# currentDetection.net
KiCad netlist of a schematic drawn in Altium Designer
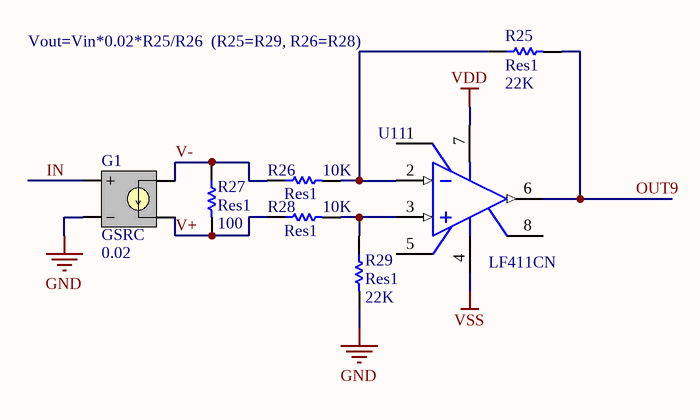
[diagram p0: currentDetection.SchDoc]

(export (version "E")
  (design (tool "Eeschema 10.0.6"))
  (components
    (comp (ref "G1")
      (value "GSRC")
      (description "Voltage Controlled Current Source")
      (fields (field (name "GAIN") "0.02") (field (name "PUBLISHER") "Altium Limited"))
      (libsource (lib "Simulation Sources") (part "GSRC"))
    )
    (comp (ref "R25")
      (value "Res1")
      (footprint "AXIAL-0.3")
      (description "Resistor")
      (fields (field (name "ALTIUM_VALUE") "22K") (field (name "PUBLISHER") "Altium Limited"))
      (libsource (lib "Miscellaneous Devices") (part "Res1"))
    )
    (comp (ref "R26")
      (value "Res1")
      (footprint "AXIAL-0.3")
      (description "Resistor")
      (fields (field (name "ALTIUM_VALUE") "10K") (field (name "PUBLISHER") "Altium Limited"))
      (libsource (lib "Miscellaneous Devices") (part "Res1"))
    )
    (comp (ref "R27")
      (value "Res1")
      (footprint "AXIAL-0.3")
      (description "Resistor")
      (fields (field (name "ALTIUM_VALUE") "100") (field (name "PUBLISHER") "Altium Limited"))
      (libsource (lib "Miscellaneous Devices") (part "Res1"))
    )
    (comp (ref "R28")
      (value "Res1")
      (footprint "AXIAL-0.3")
      (description "Resistor")
      (fields (field (name "ALTIUM_VALUE") "10K") (field (name "PUBLISHER") "Altium Limited"))
      (libsource (lib "Miscellaneous Devices") (part "Res1"))
    )
    (comp (ref "R29")
      (value "Res1")
      (footprint "AXIAL-0.3")
      (description "Resistor")
      (fields (field (name "ALTIUM_VALUE") "22K") (field (name "PUBLISHER") "Altium Limited"))
      (libsource (lib "Miscellaneous Devices") (part "Res1"))
    )
    (comp (ref "U11")
      (value "LF411CN")
      (footprint "N08E")
      (description "Low Offset, Low Drift JFET Input Operational Amplifier, 8-pin MDIP")
      (fields
        (field (name "MANUFACTURER") "National Semiconductor")
        (field (name "PUBLISHER") "Altium Limited")
      )
      (libsource (lib "NSC Amplifier") (part "LF411CN"))
    )
  )
  (nets
    (net (code "1") (name "/IN") (class "Default")
      (node (ref "G1") (pin "1") (pinfunction "NC+_1") (pintype "passive"))
    )
    (net (code "2") (name "/OUT9") (class "Default")
      (node (ref "R25") (pin "2") (pinfunction "2_2") (pintype "passive"))
      (node (ref "U11") (pin "6") (pinfunction "OUT_6") (pintype "output"))
    )
    (net (code "3") (name "/V+") (class "Default")
      (node (ref "G1") (pin "4") (pinfunction "N-_4") (pintype "passive"))
      (node (ref "R27") (pin "2") (pinfunction "2_2") (pintype "passive"))
      (node (ref "R28") (pin "1") (pinfunction "1_1") (pintype "passive"))
    )
    (net (code "4") (name "/V-") (class "Default")
      (node (ref "G1") (pin "3") (pinfunction "N+_3") (pintype "passive"))
      (node (ref "R26") (pin "1") (pinfunction "1_1") (pintype "passive"))
      (node (ref "R27") (pin "1") (pinfunction "1_1") (pintype "passive"))
    )
    (net (code "5") (name "GND") (class "Default")
      (node (ref "G1") (pin "2") (pinfunction "NC-_2") (pintype "passive"))
      (node (ref "R29") (pin "2") (pinfunction "2_2") (pintype "passive"))
    )
    (net (code "6") (name "Net-(U11-IN+)") (class "Default")
      (node (ref "R28") (pin "2") (pinfunction "2_2") (pintype "passive"))
      (node (ref "R29") (pin "1") (pinfunction "1_1") (pintype "passive"))
      (node (ref "U11") (pin "3") (pinfunction "IN+_3") (pintype "input"))
    )
    (net (code "7") (name "Net-(U11-IN-)") (class "Default")
      (node (ref "R25") (pin "1") (pinfunction "1_1") (pintype "passive"))
      (node (ref "R26") (pin "2") (pinfunction "2_2") (pintype "passive"))
      (node (ref "U11") (pin "2") (pinfunction "IN-_2") (pintype "input"))
    )
    (net (code "8") (name "VDD") (class "Default")
      (node (ref "U11") (pin "7") (pinfunction "V+_7") (pintype "power_in"))
    )
    (net (code "9") (name "VSS") (class "Default")
      (node (ref "U11") (pin "4") (pinfunction "V-_4") (pintype "power_in"))
    )
    (net (code "10") (name "unconnected-(U11-BAL-Pad1)") (class "Default")
      (node (ref "U11") (pin "1") (pinfunction "BAL_1") (pintype "passive"))
    )
    (net (code "11") (name "unconnected-(U11-BAL-Pad5)") (class "Default")
      (node (ref "U11") (pin "5") (pinfunction "BAL_5") (pintype "passive"))
    )
    (net (code "12") (name "unconnected-(U11-NC-Pad8)") (class "Default")
      (node (ref "U11") (pin "8") (pinfunction "NC_8") (pintype "passive"))
    )
  )
)
